# DBMSch.net
KiCad netlist of a schematic drawn in Altium Designer
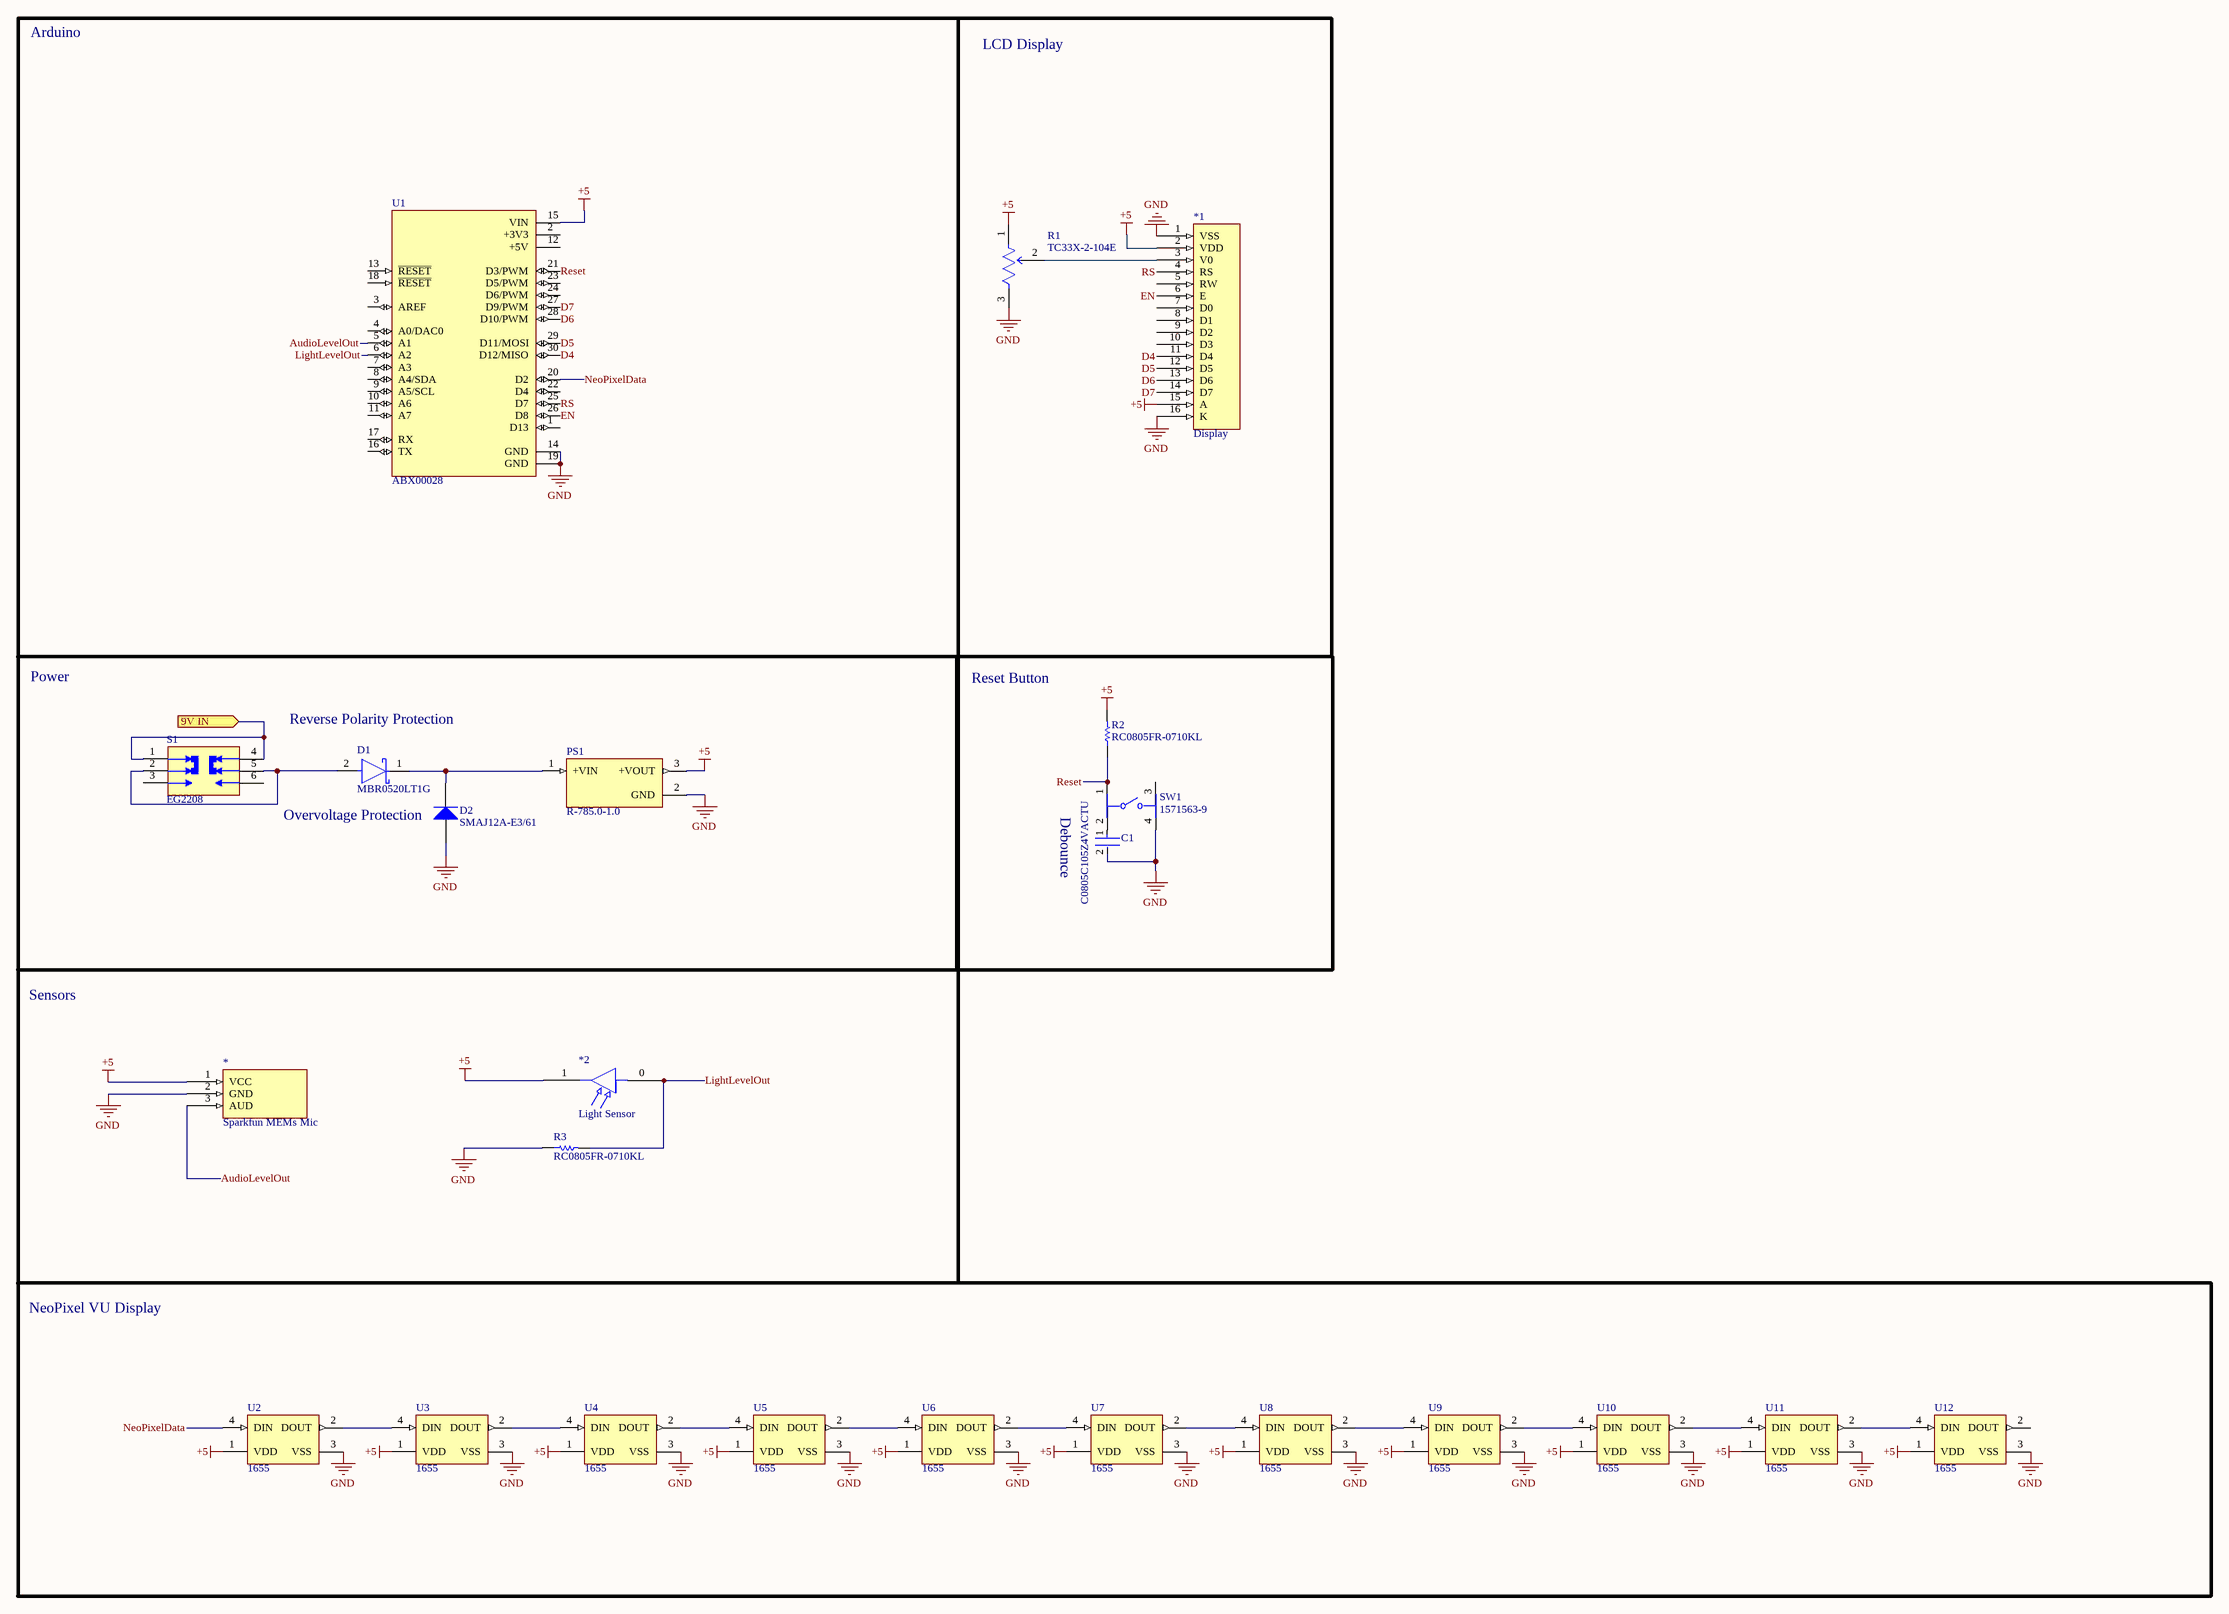
[diagram p0: DBMSch.SchDoc]

(export (version "E")
  (design (tool "Eeschema 10.0.6"))
  (components
    (comp (ref "*")
      (value "Sparkfun MEMs Mic")
      (footprint "MEMs Mic Board")
      (libsource (lib "DBM") (part "Sparkfun MEMs Mic"))
    )
    (comp (ref "*1")
      (value "Display")
      (footprint "Screen")
      (libsource (lib "RiceCookerLib") (part "Display"))
    )
    (comp (ref "*2")
      (value "Light Sensor")
      (footprint "Light Sensor")
      (libsource (lib "DBM") (part "Light Sensor"))
    )
    (comp (ref "C1")
      (value "C0805C105Z4VACTU")
      (footprint "FP-C0805C105Z4VACTU-MFG")
      (description "CAP CER 1UF 16V Y5V 0805")
      (fields (field (name "VOLTAGE") "16V") (field (name "TOLERANCE") "80%"))
      (libsource (lib "Altium Content Vault") (part "02cd4be3c70576c341d710602a673aa"))
    )
    (comp (ref "D1")
      (value "MBR0520LT1G")
      (footprint "FP-425-04-IPC_C")
      (description "DIODE SCHOTTKY 20V 500MA SOD123")
      (libsource (lib "Altium Content Vault") (part "1d6ec82d83fb6aee721767c19dac4b9"))
    )
    (comp (ref "D2")
      (value "SMAJ12A-E3/61")
      (footprint "VISH-DO-214AC-2_N")
      (fields (field (name "MANUFACTURER") "Vishay Semiconductor"))
      (libsource (lib "Altium Content Vault") (part "VISH-K1A2-2"))
    )
    (comp (ref "PS1")
      (value "R-785.0-1.0")
      (footprint "CONV_R-785.0-1.0")
      (description "1.0 Amp SIP3 Single Output")
      (fields (field (name "MF") "{'manufacturer': u'Recom Power'}"))
      (libsource (lib "R-785.0-1.0") (part "R-785.0-1.0"))
    )
    (comp (ref "R1")
      (value "TC33X-2-104E")
      (footprint "FP-TC33X-2-MFG")
      (description "TRIMMER 100K OHM 0.1W J LEAD TOP")
      (fields (field (name "TOLERANCE") "25%"))
      (libsource (lib "Altium Content Vault") (part "13357d81287629c2fd191d242cfa50c"))
    )
    (comp (ref "R2")
      (value "RC0805FR-0710KL")
      (footprint "RESC2013X60X35NL10T20")
      (description "Chip Resistor, 10 KOhm, +/- 1%, 0.125 W, -55 to 155 degC, 0805 (2012 Metric), RoHS, Tape and Reel")
      (fields (field (name "MANUFACTURER") "Yageo"))
      (libsource (lib "Altium Content Vault") (part "RES-2"))
    )
    (comp (ref "R3")
      (value "RC0805FR-0710KL")
      (footprint "RESC2013X60X35NL10T20")
      (description "Chip Resistor, 10 KOhm, +/- 1%, 0.125 W, -55 to 155 degC, 0805 (2012 Metric), RoHS, Tape and Reel")
      (fields (field (name "MANUFACTURER") "Yageo"))
      (libsource (lib "Altium Content Vault") (part "RES-2"))
    )
    (comp (ref "S1")
      (value "EG2208")
      (footprint "EG2208:SW_EG2208")
      (fields (field (name "MF") "{'manufacturer': u'E-Switch'}"))
      (libsource (lib "EG2208") (part "EG2208"))
    )
    (comp (ref "SW1")
      (value "1571563-9")
      (footprint "FP-1571563-9-MFG")
      (description "SWITCH TACTILE SPST-NO 0.05A 24V")
      (fields
        (field (name "MANUFACTURER") "TE Connectivity")
        (field (name "OCTOPART") "https://octopart.com/1571563-9-te+connectivity-41253969")
      )
      (libsource (lib "Altium Content Vault") (part "b8895f3f4cefb76e1819d2863dba89b"))
    )
    (comp (ref "U1")
      (value "ABX00028")
      (footprint "MODULE_ABX00028")
      (description "ATmega4809 Arduino Nano Every AVR AVR MCU 8-Bit Embedded Evaluation Board")
      (fields (field (name "MF") "{'manufacturer': u'Arduino'}"))
      (libsource (lib "Arduino Nano Every") (part "ABX00028"))
    )
    (comp (ref "U2")
      (value "1655")
      (footprint "ADA-RGB-1655_V")
      (fields (field (name "MANUFACTURER") "Adafruit-Industries-LLC"))
      (libsource (lib "Altium Content Vault") (part "ADA-RGB-1655-4"))
    )
    (comp (ref "U3")
      (value "1655")
      (footprint "ADA-RGB-1655_V")
      (fields (field (name "MANUFACTURER") "Adafruit-Industries-LLC"))
      (libsource (lib "Altium Content Vault") (part "ADA-RGB-1655-4"))
    )
    (comp (ref "U4")
      (value "1655")
      (footprint "ADA-RGB-1655_V")
      (fields (field (name "MANUFACTURER") "Adafruit-Industries-LLC"))
      (libsource (lib "Altium Content Vault") (part "ADA-RGB-1655-4"))
    )
    (comp (ref "U5")
      (value "1655")
      (footprint "ADA-RGB-1655_V")
      (fields (field (name "MANUFACTURER") "Adafruit-Industries-LLC"))
      (libsource (lib "Altium Content Vault") (part "ADA-RGB-1655-4"))
    )
    (comp (ref "U6")
      (value "1655")
      (footprint "ADA-RGB-1655_V")
      (fields (field (name "MANUFACTURER") "Adafruit-Industries-LLC"))
      (libsource (lib "Altium Content Vault") (part "ADA-RGB-1655-4"))
    )
    (comp (ref "U7")
      (value "1655")
      (footprint "ADA-RGB-1655_V")
      (fields (field (name "MANUFACTURER") "Adafruit-Industries-LLC"))
      (libsource (lib "Altium Content Vault") (part "ADA-RGB-1655-4"))
    )
    (comp (ref "U8")
      (value "1655")
      (footprint "ADA-RGB-1655_V")
      (fields (field (name "MANUFACTURER") "Adafruit-Industries-LLC"))
      (libsource (lib "Altium Content Vault") (part "ADA-RGB-1655-4"))
    )
    (comp (ref "U9")
      (value "1655")
      (footprint "ADA-RGB-1655_V")
      (fields (field (name "MANUFACTURER") "Adafruit-Industries-LLC"))
      (libsource (lib "Altium Content Vault") (part "ADA-RGB-1655-4"))
    )
    (comp (ref "U10")
      (value "1655")
      (footprint "ADA-RGB-1655_V")
      (fields (field (name "MANUFACTURER") "Adafruit-Industries-LLC"))
      (libsource (lib "Altium Content Vault") (part "ADA-RGB-1655-4"))
    )
    (comp (ref "U11")
      (value "1655")
      (footprint "ADA-RGB-1655_V")
      (fields (field (name "MANUFACTURER") "Adafruit-Industries-LLC"))
      (libsource (lib "Altium Content Vault") (part "ADA-RGB-1655-4"))
    )
    (comp (ref "U12")
      (value "1655")
      (footprint "ADA-RGB-1655_V")
      (fields (field (name "MANUFACTURER") "Adafruit-Industries-LLC"))
      (libsource (lib "Altium Content Vault") (part "ADA-RGB-1655-4"))
    )
  )
  (nets
    (net (code "1") (name "+5") (class "Default")
      (node (ref "*") (pin "1") (pinfunction "VCC_1") (pintype "input"))
      (node (ref "*1") (pin "15") (pinfunction "A_15") (pintype "input"))
      (node (ref "*1") (pin "2") (pinfunction "VDD_2") (pintype "input"))
      (node (ref "*2") (pin "1") (pinfunction "1_1") (pintype "passive"))
      (node (ref "PS1") (pin "3") (pinfunction "+VOUT_3") (pintype "output"))
      (node (ref "R1") (pin "1") (pinfunction "CCW_1") (pintype "passive"))
      (node (ref "R2") (pin "2") (pinfunction "2_2") (pintype "passive"))
      (node (ref "U1") (pin "15") (pinfunction "VIN_15") (pintype "power_in"))
      (node (ref "U10") (pin "1") (pinfunction "VDD_1") (pintype "power_in"))
      (node (ref "U11") (pin "1") (pinfunction "VDD_1") (pintype "power_in"))
      (node (ref "U12") (pin "1") (pinfunction "VDD_1") (pintype "power_in"))
      (node (ref "U2") (pin "1") (pinfunction "VDD_1") (pintype "power_in"))
      (node (ref "U3") (pin "1") (pinfunction "VDD_1") (pintype "power_in"))
      (node (ref "U4") (pin "1") (pinfunction "VDD_1") (pintype "power_in"))
      (node (ref "U5") (pin "1") (pinfunction "VDD_1") (pintype "power_in"))
      (node (ref "U6") (pin "1") (pinfunction "VDD_1") (pintype "power_in"))
      (node (ref "U7") (pin "1") (pinfunction "VDD_1") (pintype "power_in"))
      (node (ref "U8") (pin "1") (pinfunction "VDD_1") (pintype "power_in"))
      (node (ref "U9") (pin "1") (pinfunction "VDD_1") (pintype "power_in"))
    )
    (net (code "2") (name "/9V IN") (class "Default")
      (node (ref "S1") (pin "1") (pinfunction "1_1") (pintype "passive"))
      (node (ref "S1") (pin "4") (pinfunction "4_4") (pintype "passive"))
    )
    (net (code "3") (name "/AudioLevelOut") (class "Default")
      (node (ref "*") (pin "3") (pinfunction "AUD_3") (pintype "input"))
      (node (ref "U1") (pin "5") (pinfunction "A1_5") (pintype "bidirectional"))
    )
    (net (code "4") (name "/D4") (class "Default")
      (node (ref "*1") (pin "11") (pinfunction "D4_11") (pintype "input"))
      (node (ref "U1") (pin "30") (pinfunction "D12/MISO_30") (pintype "bidirectional"))
    )
    (net (code "5") (name "/D5") (class "Default")
      (node (ref "*1") (pin "12") (pinfunction "D5_12") (pintype "input"))
      (node (ref "U1") (pin "29") (pinfunction "D11/MOSI_29") (pintype "bidirectional"))
    )
    (net (code "6") (name "/D6") (class "Default")
      (node (ref "*1") (pin "13") (pinfunction "D6_13") (pintype "input"))
      (node (ref "U1") (pin "28") (pinfunction "D10/PWM_28") (pintype "bidirectional"))
    )
    (net (code "7") (name "/D7") (class "Default")
      (node (ref "*1") (pin "14") (pinfunction "D7_14") (pintype "input"))
      (node (ref "U1") (pin "27") (pinfunction "D9/PWM_27") (pintype "bidirectional"))
    )
    (net (code "8") (name "/EN") (class "Default")
      (node (ref "*1") (pin "6") (pinfunction "E_6") (pintype "input"))
      (node (ref "U1") (pin "26") (pinfunction "D8_26") (pintype "bidirectional"))
    )
    (net (code "9") (name "/LightLevelOut") (class "Default")
      (node (ref "*2") (pin "0") (pinfunction "0_0") (pintype "passive"))
      (node (ref "R3") (pin "2") (pinfunction "2_2") (pintype "passive"))
      (node (ref "U1") (pin "6") (pinfunction "A2_6") (pintype "bidirectional"))
    )
    (net (code "10") (name "/NeoPixelData") (class "Default")
      (node (ref "U1") (pin "20") (pinfunction "D2_20") (pintype "bidirectional"))
      (node (ref "U2") (pin "4") (pinfunction "DIN_4") (pintype "input"))
    )
    (net (code "11") (name "/RS") (class "Default")
      (node (ref "*1") (pin "4") (pinfunction "RS_4") (pintype "input"))
      (node (ref "U1") (pin "25") (pinfunction "D7_25") (pintype "bidirectional"))
    )
    (net (code "12") (name "/Reset") (class "Default")
      (node (ref "R2") (pin "1") (pinfunction "1_1") (pintype "passive"))
      (node (ref "SW1") (pin "1") (pinfunction "1_1") (pintype "passive"))
      (node (ref "U1") (pin "21") (pinfunction "D3/PWM_21") (pintype "bidirectional"))
    )
    (net (code "13") (name "GND") (class "Default")
      (node (ref "*") (pin "2") (pinfunction "GND_2") (pintype "input"))
      (node (ref "*1") (pin "1") (pinfunction "VSS_1") (pintype "input"))
      (node (ref "*1") (pin "16") (pinfunction "K_16") (pintype "input"))
      (node (ref "C1") (pin "2") (pinfunction "2_2") (pintype "passive"))
      (node (ref "D2") (pin "2") (pinfunction "A_2") (pintype "passive"))
      (node (ref "PS1") (pin "2") (pinfunction "GND_2") (pintype "power_in"))
      (node (ref "R1") (pin "3") (pinfunction "CW_3") (pintype "passive"))
      (node (ref "R3") (pin "1") (pinfunction "1_1") (pintype "passive"))
      (node (ref "SW1") (pin "4") (pinfunction "4_4") (pintype "passive"))
      (node (ref "U1") (pin "14") (pinfunction "GND_14") (pintype "power_in"))
      (node (ref "U1") (pin "19") (pinfunction "GND_19") (pintype "power_in"))
      (node (ref "U10") (pin "3") (pinfunction "VSS_3") (pintype "power_in"))
      (node (ref "U11") (pin "3") (pinfunction "VSS_3") (pintype "power_in"))
      (node (ref "U12") (pin "3") (pinfunction "VSS_3") (pintype "power_in"))
      (node (ref "U2") (pin "3") (pinfunction "VSS_3") (pintype "power_in"))
      (node (ref "U3") (pin "3") (pinfunction "VSS_3") (pintype "power_in"))
      (node (ref "U4") (pin "3") (pinfunction "VSS_3") (pintype "power_in"))
      (node (ref "U5") (pin "3") (pinfunction "VSS_3") (pintype "power_in"))
      (node (ref "U6") (pin "3") (pinfunction "VSS_3") (pintype "power_in"))
      (node (ref "U7") (pin "3") (pinfunction "VSS_3") (pintype "power_in"))
      (node (ref "U8") (pin "3") (pinfunction "VSS_3") (pintype "power_in"))
      (node (ref "U9") (pin "3") (pinfunction "VSS_3") (pintype "power_in"))
    )
    (net (code "14") (name "Net-(*1-V0)") (class "Default")
      (node (ref "*1") (pin "3") (pinfunction "V0_3") (pintype "input"))
      (node (ref "R1") (pin "2") (pinfunction "WIPER_2") (pintype "passive"))
    )
    (net (code "15") (name "Net-(C1-Pad1)") (class "Default")
      (node (ref "C1") (pin "1") (pinfunction "1_1") (pintype "passive"))
      (node (ref "SW1") (pin "2") (pinfunction "2_2") (pintype "passive"))
    )
    (net (code "16") (name "Net-(D1-A)") (class "Default")
      (node (ref "D1") (pin "2") (pinfunction "A_2") (pintype "passive"))
      (node (ref "S1") (pin "2") (pinfunction "2_2") (pintype "passive"))
      (node (ref "S1") (pin "5") (pinfunction "5_5") (pintype "passive"))
    )
    (net (code "17") (name "Net-(D1-C)") (class "Default")
      (node (ref "D1") (pin "1") (pinfunction "C_1") (pintype "passive"))
      (node (ref "D2") (pin "1") (pinfunction "K_1") (pintype "passive"))
      (node (ref "PS1") (pin "1") (pinfunction "+VIN_1") (pintype "input"))
    )
    (net (code "18") (name "Net-(U2-DOUT)") (class "Default")
      (node (ref "U2") (pin "2") (pinfunction "DOUT_2") (pintype "output"))
      (node (ref "U3") (pin "4") (pinfunction "DIN_4") (pintype "input"))
    )
    (net (code "19") (name "Net-(U3-DOUT)") (class "Default")
      (node (ref "U3") (pin "2") (pinfunction "DOUT_2") (pintype "output"))
      (node (ref "U4") (pin "4") (pinfunction "DIN_4") (pintype "input"))
    )
    (net (code "20") (name "Net-(U4-DOUT)") (class "Default")
      (node (ref "U4") (pin "2") (pinfunction "DOUT_2") (pintype "output"))
      (node (ref "U5") (pin "4") (pinfunction "DIN_4") (pintype "input"))
    )
    (net (code "21") (name "Net-(U5-DOUT)") (class "Default")
      (node (ref "U5") (pin "2") (pinfunction "DOUT_2") (pintype "output"))
      (node (ref "U6") (pin "4") (pinfunction "DIN_4") (pintype "input"))
    )
    (net (code "22") (name "Net-(U6-DOUT)") (class "Default")
      (node (ref "U6") (pin "2") (pinfunction "DOUT_2") (pintype "output"))
      (node (ref "U7") (pin "4") (pinfunction "DIN_4") (pintype "input"))
    )
    (net (code "23") (name "Net-(U7-DOUT)") (class "Default")
      (node (ref "U7") (pin "2") (pinfunction "DOUT_2") (pintype "output"))
      (node (ref "U8") (pin "4") (pinfunction "DIN_4") (pintype "input"))
    )
    (net (code "24") (name "Net-(U8-DOUT)") (class "Default")
      (node (ref "U8") (pin "2") (pinfunction "DOUT_2") (pintype "output"))
      (node (ref "U9") (pin "4") (pinfunction "DIN_4") (pintype "input"))
    )
    (net (code "25") (name "Net-(U10-DIN)") (class "Default")
      (node (ref "U10") (pin "4") (pinfunction "DIN_4") (pintype "input"))
      (node (ref "U9") (pin "2") (pinfunction "DOUT_2") (pintype "output"))
    )
    (net (code "26") (name "Net-(U10-DOUT)") (class "Default")
      (node (ref "U10") (pin "2") (pinfunction "DOUT_2") (pintype "output"))
      (node (ref "U11") (pin "4") (pinfunction "DIN_4") (pintype "input"))
    )
    (net (code "27") (name "Net-(U11-DOUT)") (class "Default")
      (node (ref "U11") (pin "2") (pinfunction "DOUT_2") (pintype "output"))
      (node (ref "U12") (pin "4") (pinfunction "DIN_4") (pintype "input"))
    )
    (net (code "28") (name "unconnected-(*1-D0-Pad7)") (class "Default")
      (node (ref "*1") (pin "7") (pinfunction "D0_7") (pintype "input"))
    )
    (net (code "29") (name "unconnected-(*1-D1-Pad8)") (class "Default")
      (node (ref "*1") (pin "8") (pinfunction "D1_8") (pintype "input"))
    )
    (net (code "30") (name "unconnected-(*1-D2-Pad9)") (class "Default")
      (node (ref "*1") (pin "9") (pinfunction "D2_9") (pintype "input"))
    )
    (net (code "31") (name "unconnected-(*1-D3-Pad10)") (class "Default")
      (node (ref "*1") (pin "10") (pinfunction "D3_10") (pintype "input"))
    )
    (net (code "32") (name "unconnected-(*1-RW-Pad5)") (class "Default")
      (node (ref "*1") (pin "5") (pinfunction "RW_5") (pintype "input"))
    )
    (net (code "33") (name "unconnected-(S1-Pad3)") (class "Default")
      (node (ref "S1") (pin "3") (pinfunction "3_3") (pintype "passive"))
    )
    (net (code "34") (name "unconnected-(S1-Pad6)") (class "Default")
      (node (ref "S1") (pin "6") (pinfunction "6_6") (pintype "passive"))
    )
    (net (code "35") (name "unconnected-(SW1-Pad3)") (class "Default")
      (node (ref "SW1") (pin "3") (pinfunction "3_3") (pintype "passive"))
    )
    (net (code "36") (name "unconnected-(U1-+3V3-Pad2)") (class "Default")
      (node (ref "U1") (pin "2") (pinfunction "+3V3_2") (pintype "power_in"))
    )
    (net (code "37") (name "unconnected-(U1-+5V-Pad12)") (class "Default")
      (node (ref "U1") (pin "12") (pinfunction "+5V_12") (pintype "power_in"))
    )
    (net (code "38") (name "unconnected-(U1-A0{slash}DAC0-Pad4)") (class "Default")
      (node (ref "U1") (pin "4") (pinfunction "A0/DAC0_4") (pintype "bidirectional"))
    )
    (net (code "39") (name "unconnected-(U1-A3-Pad7)") (class "Default")
      (node (ref "U1") (pin "7") (pinfunction "A3_7") (pintype "bidirectional"))
    )
    (net (code "40") (name "unconnected-(U1-A4{slash}SDA-Pad8)") (class "Default")
      (node (ref "U1") (pin "8") (pinfunction "A4/SDA_8") (pintype "bidirectional"))
    )
    (net (code "41") (name "unconnected-(U1-A5{slash}SCL-Pad9)") (class "Default")
      (node (ref "U1") (pin "9") (pinfunction "A5/SCL_9") (pintype "bidirectional"))
    )
    (net (code "42") (name "unconnected-(U1-A6-Pad10)") (class "Default")
      (node (ref "U1") (pin "10") (pinfunction "A6_10") (pintype "bidirectional"))
    )
    (net (code "43") (name "unconnected-(U1-A7-Pad11)") (class "Default")
      (node (ref "U1") (pin "11") (pinfunction "A7_11") (pintype "bidirectional"))
    )
    (net (code "44") (name "unconnected-(U1-AREF-Pad3)") (class "Default")
      (node (ref "U1") (pin "3") (pinfunction "AREF_3") (pintype "bidirectional"))
    )
    (net (code "45") (name "unconnected-(U1-D4-Pad22)") (class "Default")
      (node (ref "U1") (pin "22") (pinfunction "D4_22") (pintype "bidirectional"))
    )
    (net (code "46") (name "unconnected-(U1-D5{slash}PWM-Pad23)") (class "Default")
      (node (ref "U1") (pin "23") (pinfunction "D5/PWM_23") (pintype "bidirectional"))
    )
    (net (code "47") (name "unconnected-(U1-D6{slash}PWM-Pad24)") (class "Default")
      (node (ref "U1") (pin "24") (pinfunction "D6/PWM_24") (pintype "bidirectional"))
    )
    (net (code "48") (name "unconnected-(U1-D13-Pad1)") (class "Default")
      (node (ref "U1") (pin "1") (pinfunction "D13_1") (pintype "bidirectional"))
    )
    (net (code "49") (name "unconnected-(U1-RX-Pad17)") (class "Default")
      (node (ref "U1") (pin "17") (pinfunction "RX_17") (pintype "bidirectional"))
    )
    (net (code "50") (name "unconnected-(U1-TX-Pad16)") (class "Default")
      (node (ref "U1") (pin "16") (pinfunction "TX_16") (pintype "bidirectional"))
    )
    (net (code "51") (name "unconnected-(U1-~{RESET}-Pad13)") (class "Default")
      (node (ref "U1") (pin "13") (pinfunction "~{RESET}_13") (pintype "input"))
    )
    (net (code "52") (name "unconnected-(U1-~{RESET}-Pad18)") (class "Default")
      (node (ref "U1") (pin "18") (pinfunction "~{RESET}_18") (pintype "input"))
    )
    (net (code "53") (name "unconnected-(U12-DOUT-Pad2)") (class "Default")
      (node (ref "U12") (pin "2") (pinfunction "DOUT_2") (pintype "output"))
    )
  )
)
